# DL.net
KiCad netlist of a schematic drawn in Altium Designer
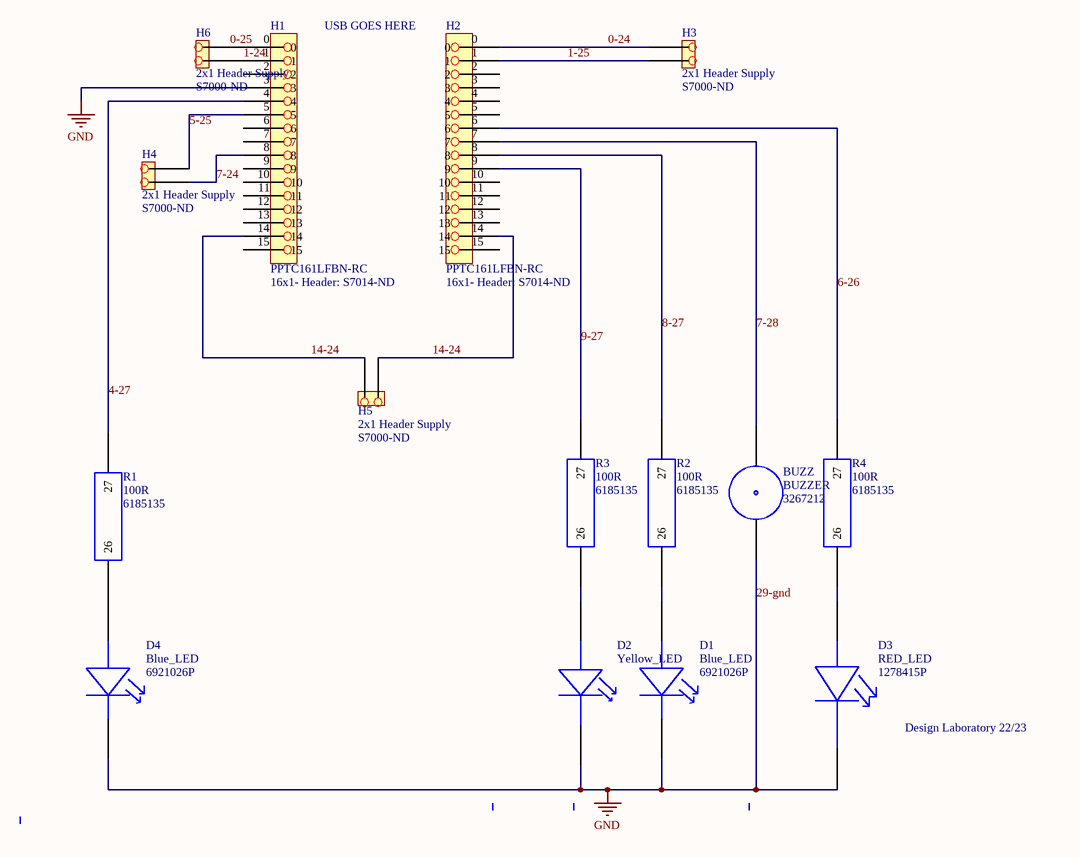
[diagram p0: DL.SchDoc]

(export (version "E")
  (design (tool "Eeschema 10.0.6"))
  (components
    (comp (ref "BUZZ")
      (value "BUZZER")
      (footprint "BUZZ")
      (description "Audio Buzzer Piezo 30Vo-p 3Vo-p 70dBA Through Hole Pin Ammo")
      (fields
        (field (name "MANUFACTURER") "TDK")
        (field (name "MANUFACTURER PART NUMBER") "PS1240P02BT")
        (field (name "SUPPLIER PART NUMBER 1") "3267212")
      )
      (libsource (lib "DL") (part "PS1240P02BT"))
    )
    (comp (ref "D1")
      (value "Blue_LED")
      (footprint "LED_BLUE")
      (description "LED BLUE CLEAR 0603 SMD")
      (fields
        (field (name "MANUFACTURER") "Vishay Lite-On")
        (field (name "MANUFACTURER PART NUMBER") "LTST-C191TBKT")
        (field (name "SUPPLIER PART NUMBER 1") "6921026P")
      )
      (libsource (lib "DL") (part "LTST-C191TBKT"))
    )
    (comp (ref "D2")
      (value "Yellow_LED")
      (footprint "LED_Yellow")
      (description "LED YELLOW CLEAR 0603 SMD")
      (fields
        (field (name "MANUFACTURER") "Vishay Lite-On")
        (field (name "MANUFACTURER PART NUMBER") "LTST-C191KSKT")
      )
      (libsource (lib "DL") (part "LTST-C191KSKT"))
    )
    (comp (ref "D3")
      (value "RED_LED")
      (footprint "LED_GREEN")
      (description "LED Uni-Color Red 639nm 2-Pin Chip LED T/R / LED RED CLEAR 0603 SMD")
      (fields
        (field (name "MANUFACTURER") "Vishay Lite-On")
        (field (name "MANUFACTURER PART NUMBER") "LTST-C191KRKT")
        (field (name "SUPPLIER PART NUMBER 1") "1278415P")
      )
      (libsource (lib "DL") (part "LTST-C191KRKT"))
    )
    (comp (ref "D4")
      (value "Blue_LED")
      (footprint "LED_BLUE")
      (description "LED BLUE CLEAR 0603 SMD")
      (fields
        (field (name "MANUFACTURER") "Vishay Lite-On")
        (field (name "MANUFACTURER PART NUMBER") "LTST-C191TBKT")
        (field (name "SUPPLIER PART NUMBER 1") "6921026P")
      )
      (libsource (lib "DL") (part "LTST-C191TBKT"))
    )
    (comp (ref "H1")
      (value "PPTC161LFBN-RC")
      (footprint "DIP32")
      (description "Sullins Connector Solutions PPTC161LFBN-RC / Conn Header Female 16POS .1\"\" T")
      (fields (field (name "MANUFACTURER") "Sullins") (field (name "16X1- HEADER") "S7014-ND"))
      (libsource (lib "") (part "PPTC161LFBN-RC_1"))
    )
    (comp (ref "H2")
      (value "PPTC161LFBN-RC")
      (footprint "DIP32")
      (description "Sullins Connector Solutions PPTC161LFBN-RC / Conn Header Female 16POS .1\"\" T")
      (fields (field (name "MANUFACTURER") "Sullins") (field (name "16X1- HEADER") "S7014-ND"))
      (libsource (lib "DL") (part "PPTC161LFBN-RC"))
    )
    (comp (ref "H3")
      (value "2x1 Header Supply")
      (footprint "Power")
      (description "Female, 2C, Straight, .100\"CC; 3.20mm Tail, No Mt. 100u\" Tin; PBT, Phos Bronze, 105 C")
      (fields
        (field (name "MANUFACTURER") "Sullins")
        (field (name "MANUFACTURER PART NUMBER") "PPTC021LFBN-RC")
        (field (name "SUPPLIER PART NUMBER 1") "S7000-ND")
      )
      (libsource (lib "") (part "PPTC021LFBN-RC_2"))
    )
    (comp (ref "H4")
      (value "2x1 Header Supply")
      (footprint "Power")
      (description "Female, 2C, Straight, .100\"CC; 3.20mm Tail, No Mt. 100u\" Tin; PBT, Phos Bronze, 105 C")
      (fields
        (field (name "MANUFACTURER") "Sullins")
        (field (name "MANUFACTURER PART NUMBER") "PPTC021LFBN-RC")
        (field (name "SUPPLIER PART NUMBER 1") "S7000-ND")
      )
      (libsource (lib "DL") (part "PPTC021LFBN-RC"))
    )
    (comp (ref "H5")
      (value "2x1 Header Supply")
      (footprint "Power")
      (description "Female, 2C, Straight, .100\"CC; 3.20mm Tail, No Mt. 100u\" Tin; PBT, Phos Bronze, 105 C")
      (fields
        (field (name "MANUFACTURER") "Sullins")
        (field (name "MANUFACTURER PART NUMBER") "PPTC021LFBN-RC")
        (field (name "SUPPLIER PART NUMBER 1") "S7000-ND")
      )
      (libsource (lib "") (part "PPTC021LFBN-RC_1"))
    )
    (comp (ref "H6")
      (value "2x1 Header Supply")
      (footprint "Power")
      (description "Female, 2C, Straight, .100\"CC; 3.20mm Tail, No Mt. 100u\" Tin; PBT, Phos Bronze, 105 C")
      (fields
        (field (name "MANUFACTURER") "Sullins")
        (field (name "MANUFACTURER PART NUMBER") "PPTC021LFBN-RC")
        (field (name "SUPPLIER PART NUMBER 1") "S7000-ND")
      )
      (libsource (lib "DL") (part "PPTC021LFBN-RC"))
    )
    (comp (ref "R1")
      (value "100R")
      (footprint "R0805")
      (description "Res Thick Film 0805 100 Ohm 1% 1/8W ±100ppm/°C Molded SMD Paper T/R")
      (fields
        (field (name "MANUFACTURER") "Yageo")
        (field (name "MANUFACTURER PART NUMBER") "RC0805FR-07100RL")
        (field (name "SUPPLIER PART NUMBER 1") "6185135")
      )
      (libsource (lib "DL") (part "RC0805FR-07100RL"))
    )
    (comp (ref "R2")
      (value "100R")
      (footprint "R0805")
      (description "Res Thick Film 0805 100 Ohm 1% 1/8W ±100ppm/°C Molded SMD Paper T/R")
      (fields
        (field (name "MANUFACTURER") "Yageo")
        (field (name "MANUFACTURER PART NUMBER") "RC0805FR-07100RL")
        (field (name "SUPPLIER PART NUMBER 1") "6185135")
      )
      (libsource (lib "DL") (part "RC0805FR-07100RL"))
    )
    (comp (ref "R3")
      (value "100R")
      (footprint "R0805")
      (description "Res Thick Film 0805 100 Ohm 1% 1/8W ±100ppm/°C Molded SMD Paper T/R")
      (fields
        (field (name "MANUFACTURER") "Yageo")
        (field (name "MANUFACTURER PART NUMBER") "RC0805FR-07100RL")
        (field (name "SUPPLIER PART NUMBER 1") "6185135")
      )
      (libsource (lib "DL") (part "RC0805FR-07100RL"))
    )
    (comp (ref "R4")
      (value "100R")
      (footprint "R0805")
      (description "Res Thick Film 0805 100 Ohm 1% 1/8W ±100ppm/°C Molded SMD Paper T/R")
      (fields
        (field (name "MANUFACTURER") "Yageo")
        (field (name "MANUFACTURER PART NUMBER") "RC0805FR-07100RL")
        (field (name "SUPPLIER PART NUMBER 1") "6185135")
      )
      (libsource (lib "DL") (part "RC0805FR-07100RL"))
    )
  )
  (nets
    (net (code "1") (name "/0-24") (class "Default")
      (node (ref "H2") (pin "0") (pinfunction "0_0") (pintype "passive"))
      (node (ref "H3") (pin "24") (pinfunction "24_24") (pintype "passive"))
    )
    (net (code "3") (name "/1-24") (class "Default")
      (node (ref "H1") (pin "1") (pinfunction "1_1") (pintype "passive"))
      (node (ref "H6") (pin "24") (pinfunction "24_24") (pintype "passive"))
    )
    (net (code "4") (name "/1-25") (class "Default")
      (node (ref "H2") (pin "1") (pinfunction "1_1") (pintype "passive"))
      (node (ref "H3") (pin "25") (pinfunction "25_25") (pintype "passive"))
    )
    (net (code "5") (name "/4-27") (class "Default")
      (node (ref "H1") (pin "4") (pinfunction "4_4") (pintype "passive"))
      (node (ref "R1") (pin "27") (pinfunction "27_27") (pintype "passive"))
    )
    (net (code "6") (name "/5-25") (class "Default")
      (node (ref "H1") (pin "5") (pinfunction "5_5") (pintype "passive"))
      (node (ref "H4") (pin "25") (pinfunction "25_25") (pintype "passive"))
    )
    (net (code "7") (name "/6-26") (class "Default")
      (node (ref "H2") (pin "6") (pinfunction "6_6") (pintype "passive"))
      (node (ref "R4") (pin "27") (pinfunction "27_27") (pintype "passive"))
    )
    (net (code "8") (name "/7-24") (class "Default")
      (node (ref "H1") (pin "8") (pinfunction "8_8") (pintype "passive"))
      (node (ref "H4") (pin "24") (pinfunction "24_24") (pintype "passive"))
    )
    (net (code "9") (name "/7-28") (class "Default")
      (node (ref "BUZZ") (pin "29") (pinfunction "29_29") (pintype "passive"))
      (node (ref "H2") (pin "7") (pinfunction "7_7") (pintype "passive"))
    )
    (net (code "10") (name "/8-27") (class "Default")
      (node (ref "H2") (pin "8") (pinfunction "8_8") (pintype "passive"))
      (node (ref "R2") (pin "27") (pinfunction "27_27") (pintype "passive"))
    )
    (net (code "11") (name "/9-27") (class "Default")
      (node (ref "H2") (pin "9") (pinfunction "9_9") (pintype "passive"))
      (node (ref "R3") (pin "27") (pinfunction "27_27") (pintype "passive"))
    )
    (net (code "12") (name "/14-24") (class "Default")
      (node (ref "H1") (pin "14") (pinfunction "14_14") (pintype "passive"))
      (node (ref "H2") (pin "14") (pinfunction "14_14") (pintype "passive"))
      (node (ref "H5") (pin "24") (pinfunction "24_24") (pintype "passive"))
      (node (ref "H5") (pin "25") (pinfunction "25_25") (pintype "passive"))
    )
    (net (code "13") (name "GND") (class "Default")
      (node (ref "BUZZ") (pin "28") (pinfunction "28_28") (pintype "passive"))
      (node (ref "D1") (pin "21") (pinfunction "21_21") (pintype "passive"))
      (node (ref "D2") (pin "22") (pinfunction "22_22") (pintype "passive"))
      (node (ref "D3") (pin "18") (pinfunction "18_18") (pintype "passive"))
      (node (ref "D4") (pin "21") (pinfunction "21_21") (pintype "passive"))
      (node (ref "H1") (pin "3") (pinfunction "3_3") (pintype "passive"))
    )
    (net (code "14") (name "Net-(D1-Pad20)") (class "Default")
      (node (ref "D1") (pin "20") (pinfunction "20_20") (pintype "passive"))
      (node (ref "R2") (pin "26") (pinfunction "26_26") (pintype "passive"))
    )
    (net (code "15") (name "Net-(D2-Pad23)") (class "Default")
      (node (ref "D2") (pin "23") (pinfunction "23_23") (pintype "passive"))
      (node (ref "R3") (pin "26") (pinfunction "26_26") (pintype "passive"))
    )
    (net (code "16") (name "Net-(D3-Pad19)") (class "Default")
      (node (ref "D3") (pin "19") (pinfunction "19_19") (pintype "passive"))
      (node (ref "R4") (pin "26") (pinfunction "26_26") (pintype "passive"))
    )
    (net (code "17") (name "Net-(D4-Pad20)") (class "Default")
      (node (ref "D4") (pin "20") (pinfunction "20_20") (pintype "passive"))
      (node (ref "R1") (pin "26") (pinfunction "26_26") (pintype "passive"))
    )
    (net (code "18") (name "Net-(H1-Pad0)") (class "Default")
      (node (ref "H1") (pin "0") (pinfunction "0_0") (pintype "passive"))
      (node (ref "H6") (pin "25") (pinfunction "25_25") (pintype "passive"))
    )
    (net (code "19") (name "unconnected-(H1-Pad2)") (class "Default")
      (node (ref "H1") (pin "2") (pinfunction "2_2") (pintype "passive"))
    )
    (net (code "20") (name "unconnected-(H1-Pad6)") (class "Default")
      (node (ref "H1") (pin "6") (pinfunction "6_6") (pintype "passive"))
    )
    (net (code "21") (name "unconnected-(H1-Pad7)") (class "Default")
      (node (ref "H1") (pin "7") (pinfunction "7_7") (pintype "passive"))
    )
    (net (code "22") (name "unconnected-(H1-Pad9)") (class "Default")
      (node (ref "H1") (pin "9") (pinfunction "9_9") (pintype "passive"))
    )
    (net (code "23") (name "unconnected-(H1-Pad10)") (class "Default")
      (node (ref "H1") (pin "10") (pinfunction "10_10") (pintype "passive"))
    )
    (net (code "24") (name "unconnected-(H1-Pad11)") (class "Default")
      (node (ref "H1") (pin "11") (pinfunction "11_11") (pintype "passive"))
    )
    (net (code "25") (name "unconnected-(H1-Pad12)") (class "Default")
      (node (ref "H1") (pin "12") (pinfunction "12_12") (pintype "passive"))
    )
    (net (code "26") (name "unconnected-(H1-Pad13)") (class "Default")
      (node (ref "H1") (pin "13") (pinfunction "13_13") (pintype "passive"))
    )
    (net (code "27") (name "unconnected-(H1-Pad15)") (class "Default")
      (node (ref "H1") (pin "15") (pinfunction "15_15") (pintype "passive"))
    )
    (net (code "28") (name "unconnected-(H2-Pad2)") (class "Default")
      (node (ref "H2") (pin "2") (pinfunction "2_2") (pintype "passive"))
    )
    (net (code "29") (name "unconnected-(H2-Pad3)") (class "Default")
      (node (ref "H2") (pin "3") (pinfunction "3_3") (pintype "passive"))
    )
    (net (code "30") (name "unconnected-(H2-Pad4)") (class "Default")
      (node (ref "H2") (pin "4") (pinfunction "4_4") (pintype "passive"))
    )
    (net (code "31") (name "unconnected-(H2-Pad5)") (class "Default")
      (node (ref "H2") (pin "5") (pinfunction "5_5") (pintype "passive"))
    )
    (net (code "32") (name "unconnected-(H2-Pad10)") (class "Default")
      (node (ref "H2") (pin "10") (pinfunction "10_10") (pintype "passive"))
    )
    (net (code "33") (name "unconnected-(H2-Pad11)") (class "Default")
      (node (ref "H2") (pin "11") (pinfunction "11_11") (pintype "passive"))
    )
    (net (code "34") (name "unconnected-(H2-Pad12)") (class "Default")
      (node (ref "H2") (pin "12") (pinfunction "12_12") (pintype "passive"))
    )
    (net (code "35") (name "unconnected-(H2-Pad13)") (class "Default")
      (node (ref "H2") (pin "13") (pinfunction "13_13") (pintype "passive"))
    )
    (net (code "36") (name "unconnected-(H2-Pad15)") (class "Default")
      (node (ref "H2") (pin "15") (pinfunction "15_15") (pintype "passive"))
    )
  )
)
